# TSL2561_Stemma.net
KiCad netlist of a schematic drawn in EAGLE
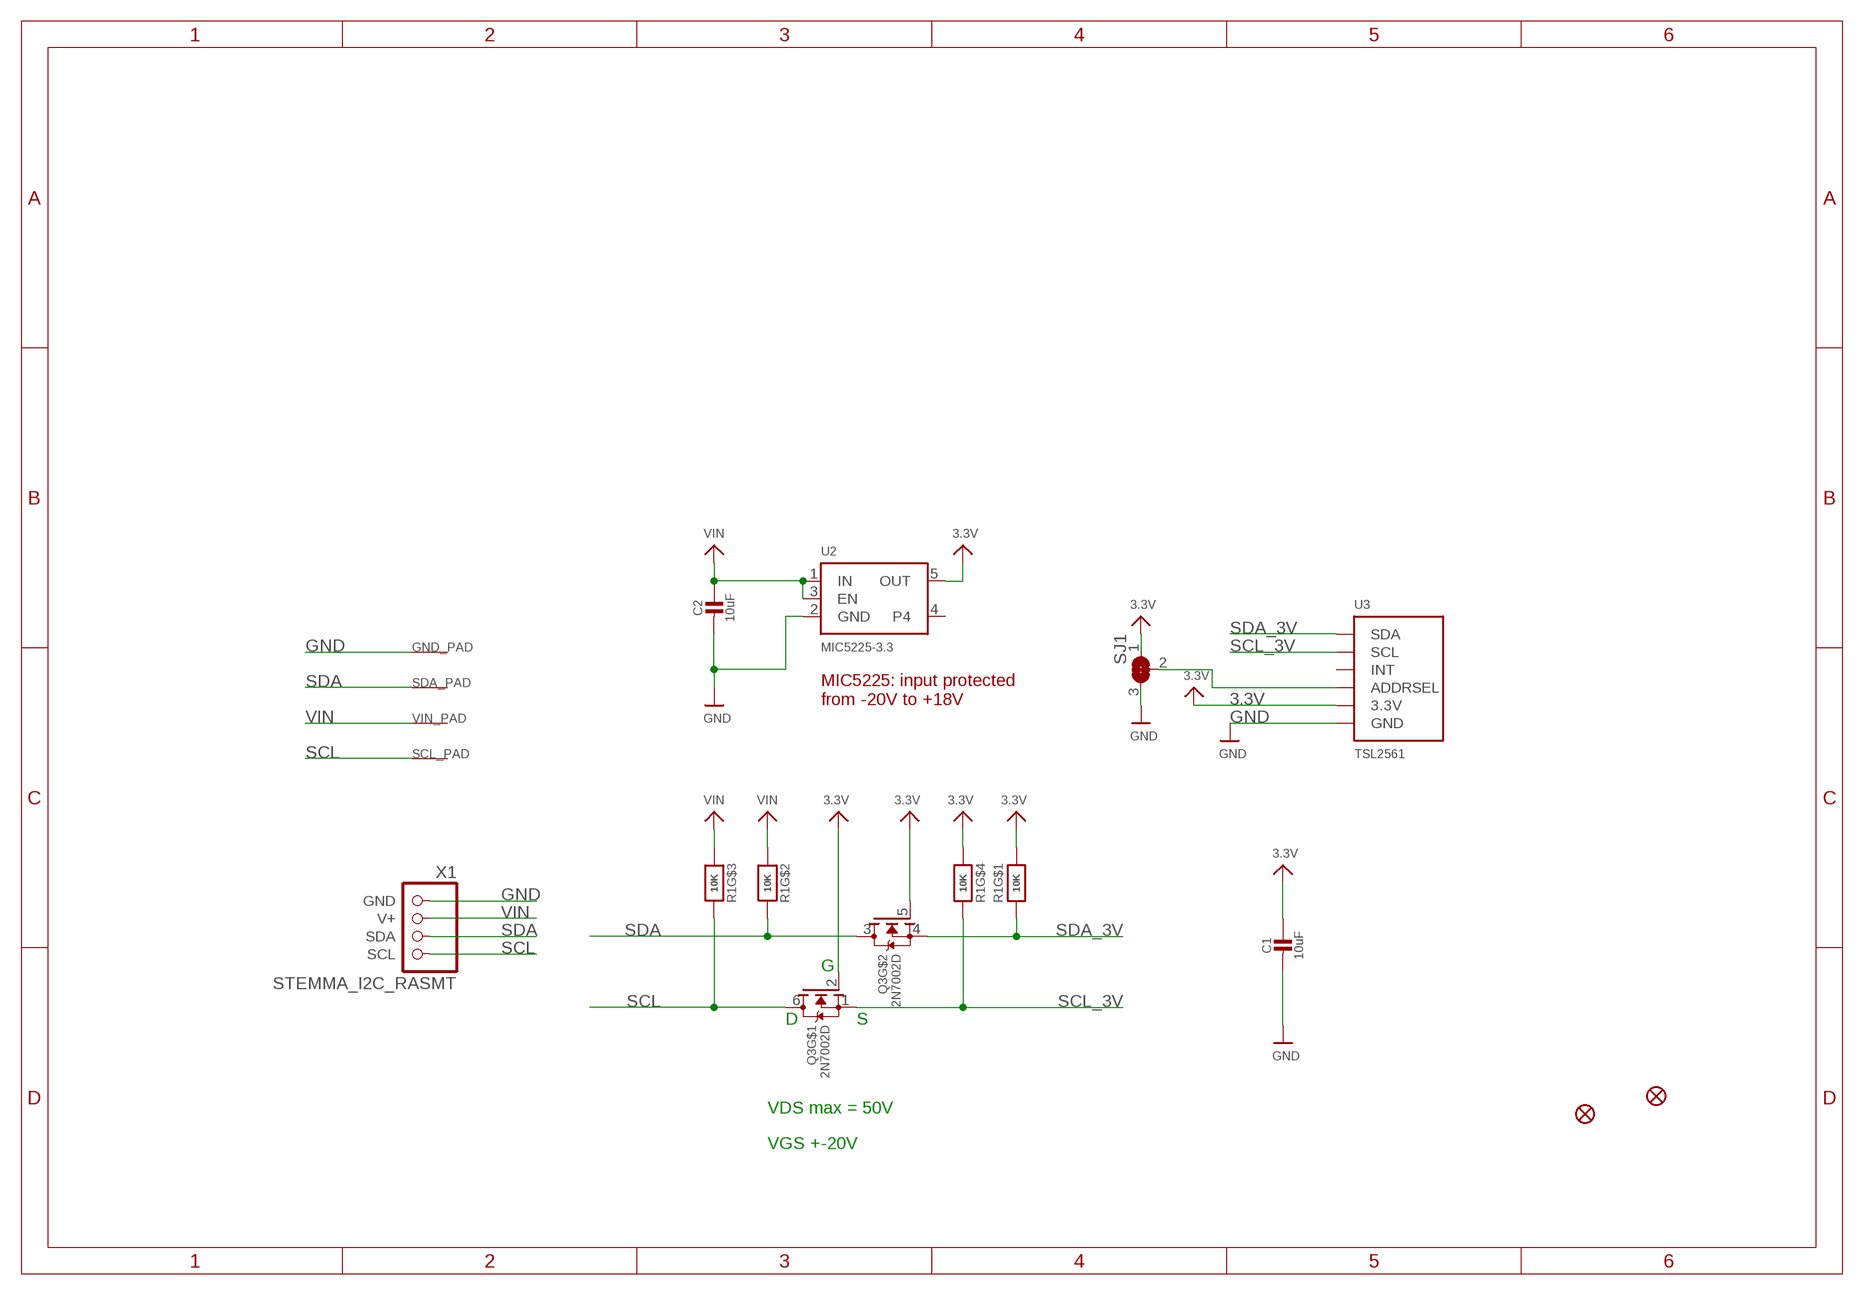
[diagram p0: schematic, sheet 1]

(export (version "E")
  (design (tool "Eeschema 10.0.6"))
  (components
    (comp (ref "C1")
      (value "10uF")
      (footprint "eagle-import:0805-NO")
      (libsource (lib "eagle-import") (part "CAP_CERAMIC0805-NOOUTLINE"))
    )
    (comp (ref "C2")
      (value "10uF")
      (footprint "eagle-import:0805-NO")
      (libsource (lib "eagle-import") (part "CAP_CERAMIC0805-NOOUTLINE"))
    )
    (comp (ref "FID1")
      (value "FIDUCIAL_1MM")
      (footprint "eagle-import:FIDUCIAL_1MM")
      (libsource (lib "eagle-import") (part "FIDUCIAL_1MM"))
    )
    (comp (ref "FID2")
      (value "FIDUCIAL_1MM")
      (footprint "eagle-import:FIDUCIAL_1MM")
      (libsource (lib "eagle-import") (part "FIDUCIAL_1MM"))
    )
    (comp (ref "GND_PAD")
      (value "SEWTAP-ALLIGATOR")
      (footprint "eagle-import:SEWALLI")
      (libsource (lib "eagle-import") (part "SEWTAP-ALLIGATOR"))
    )
    (comp (ref "Q3")
      (value "2N7002D")
      (footprint "eagle-import:SOT363")
      (libsource (lib "eagle-import") (part "MOSFET-N_DUAL"))
    )
    (comp (ref "R1")
      (value "10K")
      (footprint "eagle-import:RESPACK_4X0603")
      (libsource (lib "eagle-import") (part "RESISTOR_4PACK"))
    )
    (comp (ref "SCL_PAD")
      (value "SEWTAP-ALLIGATOR")
      (footprint "eagle-import:SEWALLI")
      (libsource (lib "eagle-import") (part "SEWTAP-ALLIGATOR"))
    )
    (comp (ref "SDA_PAD")
      (value "SEWTAP-ALLIGATOR")
      (footprint "eagle-import:SEWALLI")
      (libsource (lib "eagle-import") (part "SEWTAP-ALLIGATOR"))
    )
    (comp (ref "SJ1")
      (value "SOLDERJUMPER_2WAY")
      (footprint "eagle-import:SOLDERJUMPER_2WAY_OPEN_NOPASTE")
      (libsource (lib "eagle-import") (part "SOLDERJUMPER_2WAY"))
    )
    (comp (ref "U2")
      (value "MIC5225-3.3")
      (footprint "eagle-import:SOT23-5")
      (libsource (lib "eagle-import") (part "VREG_SOT23-5"))
    )
    (comp (ref "U3")
      (value "TSL2561")
      (footprint "eagle-import:TSL2561_FN")
      (libsource (lib "eagle-import") (part "LIGHT_TSL2561"))
    )
    (comp (ref "VIN_PAD")
      (value "SEWTAP-ALLIGATOR")
      (footprint "eagle-import:SEWALLI")
      (libsource (lib "eagle-import") (part "SEWTAP-ALLIGATOR"))
    )
    (comp (ref "X1")
      (value "STEMMA_I2C_RASMT")
      (footprint "eagle-import:JSTPH4")
      (libsource (lib "eagle-import") (part "STEMMA_I2C_RASMT"))
    )
  )
  (nets
    (net (code "1") (name "/SCL") (class "Default")
      (node (ref "Q3") (pin "6") (pinfunction "D_6") (pintype "bidirectional"))
      (node (ref "R1") (pin "6") (pinfunction "2_6") (pintype "passive"))
      (node (ref "SCL_PAD") (pin "P$1") (pinfunction "SEW_P$1") (pintype "bidirectional"))
      (node (ref "X1") (pin "4") (pinfunction "SCL_4") (pintype "passive"))
    )
    (net (code "2") (name "/SCL_3V") (class "Default")
      (node (ref "Q3") (pin "1") (pinfunction "S_1") (pintype "bidirectional"))
      (node (ref "R1") (pin "4") (pinfunction "1_4") (pintype "passive"))
      (node (ref "U3") (pin "CLK") (pinfunction "SCL_CLK") (pintype "bidirectional"))
    )
    (net (code "3") (name "/SDA") (class "Default")
      (node (ref "Q3") (pin "3") (pinfunction "D_3") (pintype "bidirectional"))
      (node (ref "R1") (pin "7") (pinfunction "2_7") (pintype "passive"))
      (node (ref "SDA_PAD") (pin "P$1") (pinfunction "SEW_P$1") (pintype "bidirectional"))
      (node (ref "X1") (pin "3") (pinfunction "SDA_3") (pintype "passive"))
    )
    (net (code "4") (name "/SDA_3V") (class "Default")
      (node (ref "Q3") (pin "4") (pinfunction "S_4") (pintype "bidirectional"))
      (node (ref "R1") (pin "8") (pinfunction "2_8") (pintype "passive"))
      (node (ref "U3") (pin "DATA") (pinfunction "SDA_DATA") (pintype "bidirectional"))
    )
    (net (code "5") (name "3.3V") (class "Default")
      (node (ref "C1") (pin "1") (pinfunction "1_1") (pintype "passive"))
      (node (ref "Q3") (pin "2") (pinfunction "G_2") (pintype "bidirectional"))
      (node (ref "Q3") (pin "5") (pinfunction "G_5") (pintype "bidirectional"))
      (node (ref "R1") (pin "1") (pinfunction "1_1") (pintype "passive"))
      (node (ref "R1") (pin "5") (pinfunction "2_5") (pintype "passive"))
      (node (ref "SJ1") (pin "1") (pinfunction "1_1") (pintype "passive"))
      (node (ref "U2") (pin "5") (pinfunction "OUT_5") (pintype "power_in"))
      (node (ref "U3") (pin "VDD") (pinfunction "3.3V_VDD") (pintype "bidirectional"))
    )
    (net (code "6") (name "GND") (class "Default")
      (node (ref "C1") (pin "2") (pinfunction "2_2") (pintype "passive"))
      (node (ref "C2") (pin "2") (pinfunction "2_2") (pintype "passive"))
      (node (ref "GND_PAD") (pin "P$1") (pinfunction "SEW_P$1") (pintype "bidirectional"))
      (node (ref "SJ1") (pin "3") (pinfunction "3_3") (pintype "passive"))
      (node (ref "U2") (pin "2") (pinfunction "GND_2") (pintype "power_in"))
      (node (ref "U3") (pin "VSS") (pinfunction "GND_VSS") (pintype "bidirectional"))
      (node (ref "X1") (pin "1") (pinfunction "GND_1") (pintype "passive"))
    )
    (net (code "7") (name "Net-(U3-ADDRSEL)") (class "Default")
      (node (ref "SJ1") (pin "2") (pinfunction "2_2") (pintype "passive"))
      (node (ref "U3") (pin "ADR") (pinfunction "ADDRSEL_ADR") (pintype "bidirectional"))
    )
    (net (code "8") (name "VIN") (class "Default")
      (node (ref "C2") (pin "1") (pinfunction "1_1") (pintype "passive"))
      (node (ref "R1") (pin "2") (pinfunction "1_2") (pintype "passive"))
      (node (ref "R1") (pin "3") (pinfunction "1_3") (pintype "passive"))
      (node (ref "U2") (pin "1") (pinfunction "IN_1") (pintype "power_in"))
      (node (ref "U2") (pin "3") (pinfunction "EN_3") (pintype "input"))
      (node (ref "VIN_PAD") (pin "P$1") (pinfunction "SEW_P$1") (pintype "bidirectional"))
      (node (ref "X1") (pin "2") (pinfunction "V+_2") (pintype "passive"))
    )
    (net (code "9") (name "unconnected-(U2-P4-Pad4)") (class "Default")
      (node (ref "U2") (pin "4") (pinfunction "P4_4") (pintype "bidirectional"))
    )
    (net (code "10") (name "unconnected-(U3-PadINT)") (class "Default")
      (node (ref "U3") (pin "INT") (pinfunction "INT_INT") (pintype "bidirectional"))
    )
  )
)
